# 220v_sensor.net
KiCad netlist of a schematic drawn in EAGLE
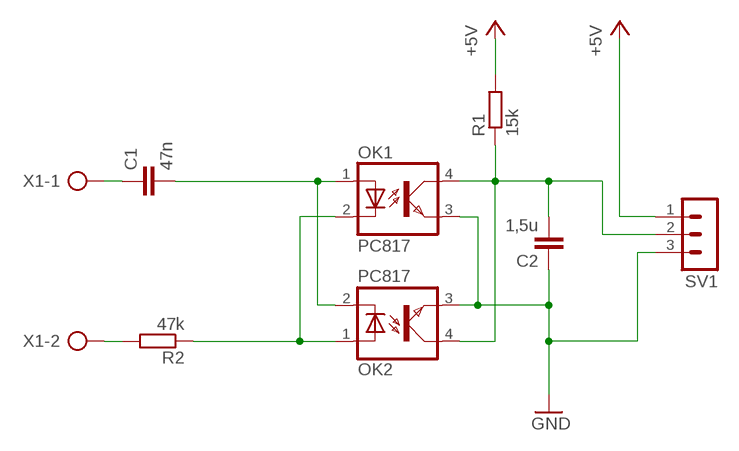
[diagram p0: schematic, sheet 1]

(export (version "E")
  (design (tool "Eeschema 10.0.6"))
  (components
    (comp (ref "C1")
      (value "47n")
      (footprint "eagle-import:C075-032X103")
      (libsource (lib "eagle-import") (part "C-EU075-032X103"))
    )
    (comp (ref "C2")
      (value "1,5u")
      (footprint "eagle-import:C075-032X103")
      (libsource (lib "eagle-import") (part "C-EU075-032X103"))
    )
    (comp (ref "OK1")
      (value "PC817")
      (footprint "eagle-import:DIL04")
      (fields (field (name "MPN") "PC817X4J000F"))
      (libsource (lib "eagle-import") (part "PC817"))
    )
    (comp (ref "OK2")
      (value "PC817")
      (footprint "eagle-import:DIL04")
      (fields (field (name "MPN") "PC817X4J000F"))
      (libsource (lib "eagle-import") (part "PC817"))
    )
    (comp (ref "R1")
      (value "15k")
      (footprint "eagle-import:0207_15")
      (libsource (lib "eagle-import") (part "R-EU_0207/15"))
    )
    (comp (ref "R2")
      (value "47k")
      (footprint "eagle-import:0207_15")
      (libsource (lib "eagle-import") (part "R-EU_0207/15"))
    )
    (comp (ref "SV1")
      (value "MA03-1")
      (footprint "eagle-import:MA03-1")
      (libsource (lib "eagle-import") (part "MA03-1"))
    )
    (comp (ref "X1")
      (value "AK300/2")
      (footprint "eagle-import:AK300_2")
      (libsource (lib "eagle-import") (part "AK300/2"))
    )
  )
  (nets
    (net (code "1") (name "+5V") (class "Default")
      (node (ref "R1") (pin "2") (pinfunction "2_2") (pintype "passive"))
      (node (ref "SV1") (pin "1") (pinfunction "1_1") (pintype "passive"))
    )
    (net (code "2") (name "GND") (class "Default")
      (node (ref "C2") (pin "1") (pinfunction "1_1") (pintype "passive"))
      (node (ref "OK1") (pin "3") (pinfunction "EMIT_3") (pintype "passive"))
      (node (ref "OK2") (pin "3") (pinfunction "EMIT_3") (pintype "passive"))
      (node (ref "SV1") (pin "3") (pinfunction "3_3") (pintype "passive"))
    )
    (net (code "3") (name "Net-(OK1-A)") (class "Default")
      (node (ref "C1") (pin "2") (pinfunction "2_2") (pintype "passive"))
      (node (ref "OK1") (pin "1") (pinfunction "A_1") (pintype "passive"))
      (node (ref "OK2") (pin "2") (pinfunction "C_2") (pintype "passive"))
    )
    (net (code "4") (name "Net-(OK1-C)") (class "Default")
      (node (ref "OK1") (pin "2") (pinfunction "C_2") (pintype "passive"))
      (node (ref "OK2") (pin "1") (pinfunction "A_1") (pintype "passive"))
      (node (ref "R2") (pin "1") (pinfunction "1_1") (pintype "passive"))
    )
    (net (code "5") (name "Net-(OK1-COL)") (class "Default")
      (node (ref "C2") (pin "2") (pinfunction "2_2") (pintype "passive"))
      (node (ref "OK1") (pin "4") (pinfunction "COL_4") (pintype "passive"))
      (node (ref "OK2") (pin "4") (pinfunction "COL_4") (pintype "passive"))
      (node (ref "R1") (pin "1") (pinfunction "1_1") (pintype "passive"))
      (node (ref "SV1") (pin "2") (pinfunction "2_2") (pintype "passive"))
    )
    (net (code "6") (name "Net-(X1A-KL)") (class "Default")
      (node (ref "C1") (pin "1") (pinfunction "1_1") (pintype "passive"))
      (node (ref "X1") (pin "1") (pinfunction "KL_1") (pintype "passive"))
    )
    (net (code "7") (name "Net-(X1B-KL)") (class "Default")
      (node (ref "R2") (pin "2") (pinfunction "2_2") (pintype "passive"))
      (node (ref "X1") (pin "2") (pinfunction "KL_2") (pintype "passive"))
    )
  )
)
